# Sauna.net
KiCad netlist of a schematic drawn in EAGLE
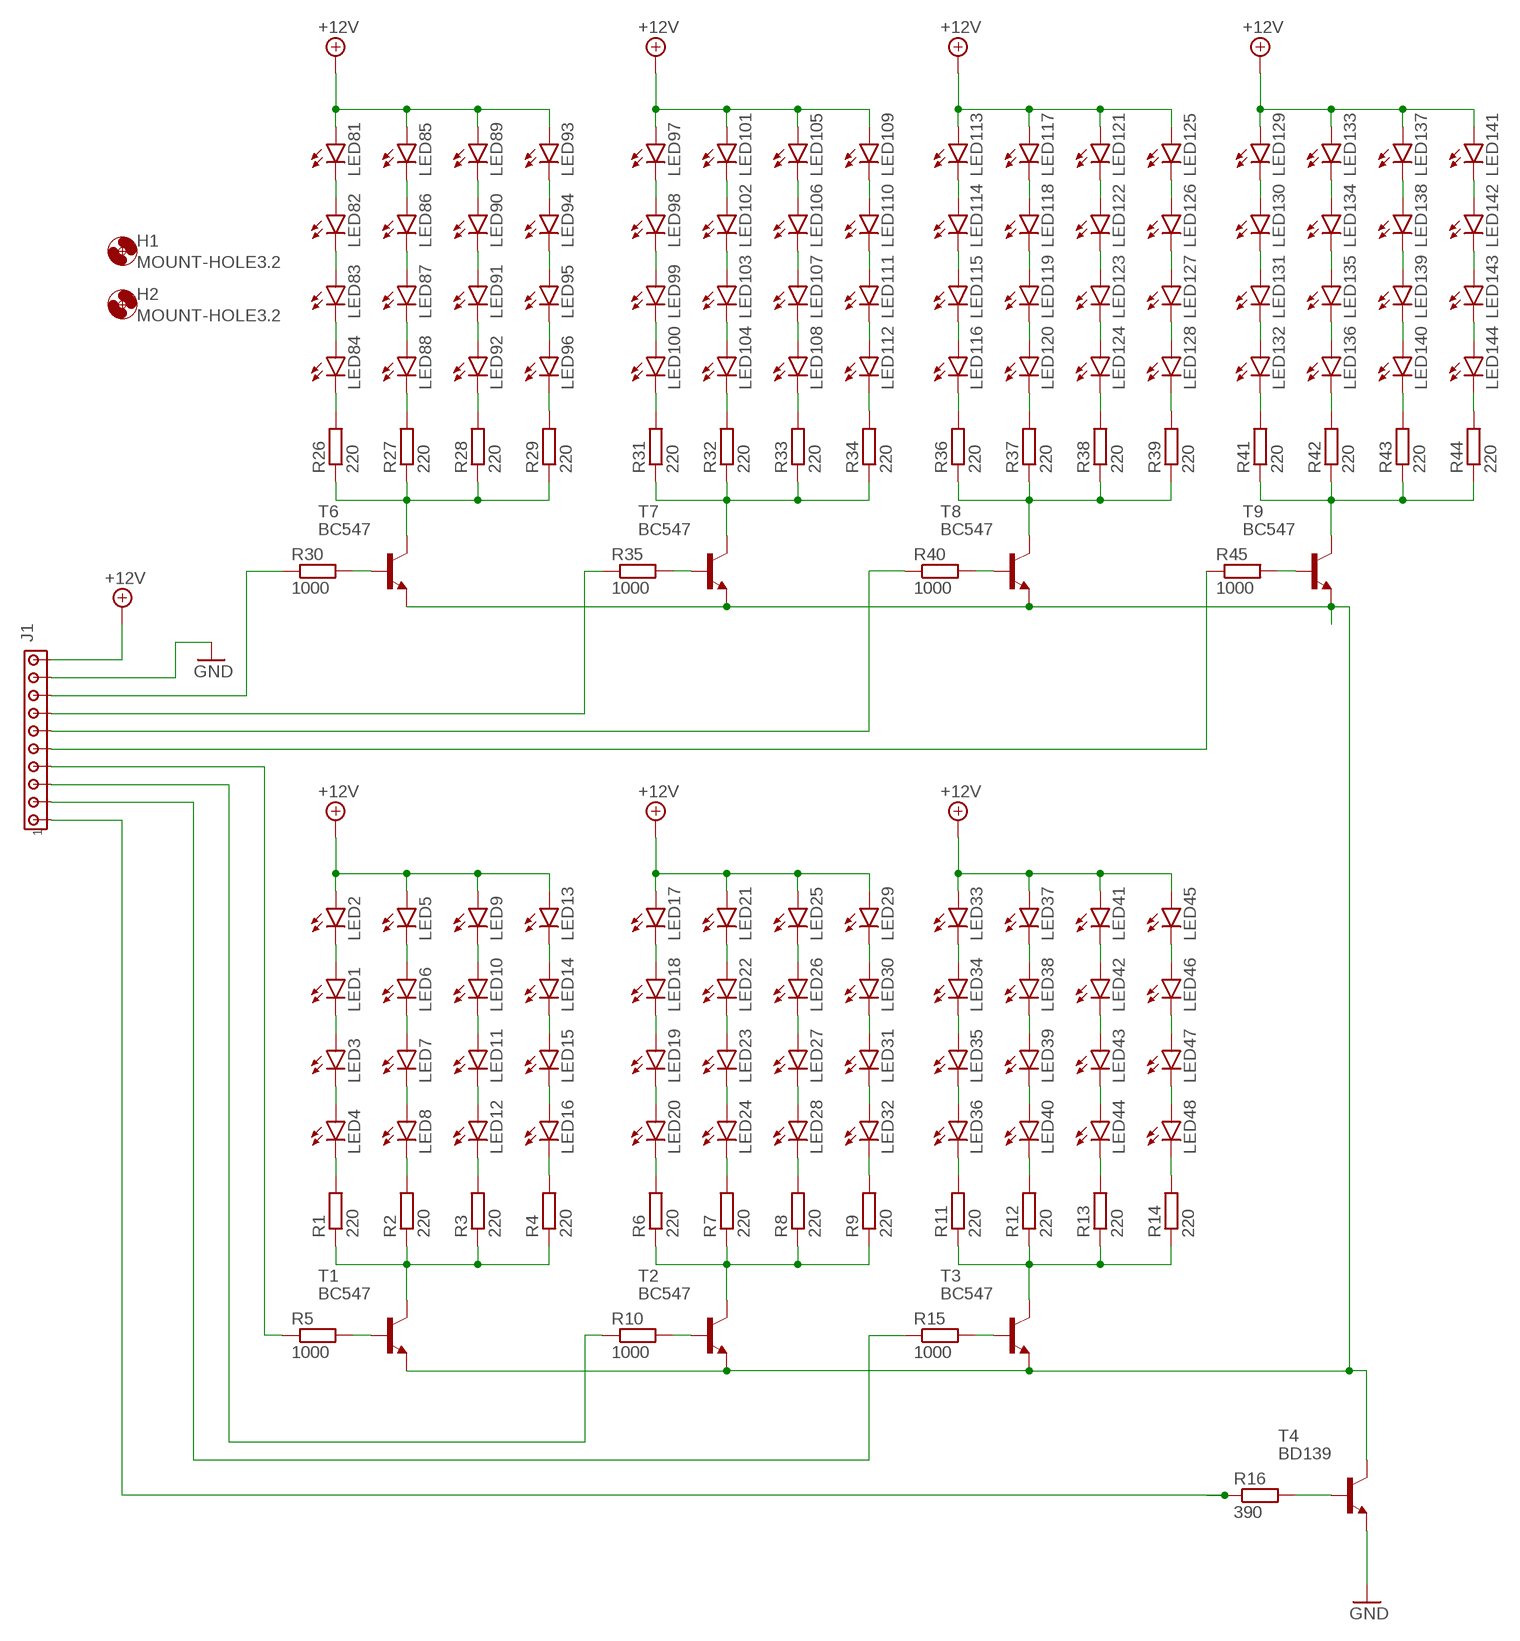
[diagram p0: schematic, sheet 1]

(export (version "E")
  (design (tool "Eeschema 10.0.6"))
  (components
    (comp (ref "H1")
      (value "MOUNT-HOLE3.2")
      (footprint "eagle-import:3,2")
      (libsource (lib "eagle-import") (part "MOUNT-HOLE3.2"))
    )
    (comp (ref "H2")
      (value "MOUNT-HOLE3.2")
      (footprint "eagle-import:3,2")
      (libsource (lib "eagle-import") (part "MOUNT-HOLE3.2"))
    )
    (comp (ref "J1")
      (value "MTA10-100")
      (footprint "eagle-import:10X10MTA")
      (libsource (lib "eagle-import") (part "MTA10-100"))
    )
    (comp (ref "LED1")
      (value "LED5MM")
      (footprint "eagle-import:LED5MM")
      (libsource (lib "eagle-import") (part "LED5MM"))
    )
    (comp (ref "LED2")
      (value "LED5MM")
      (footprint "eagle-import:LED5MM")
      (libsource (lib "eagle-import") (part "LED5MM"))
    )
    (comp (ref "LED3")
      (value "LED5MM")
      (footprint "eagle-import:LED5MM")
      (libsource (lib "eagle-import") (part "LED5MM"))
    )
    (comp (ref "LED4")
      (value "LED5MM")
      (footprint "eagle-import:LED5MM")
      (libsource (lib "eagle-import") (part "LED5MM"))
    )
    (comp (ref "LED5")
      (value "LED5MM")
      (footprint "eagle-import:LED5MM")
      (libsource (lib "eagle-import") (part "LED5MM"))
    )
    (comp (ref "LED6")
      (value "LED5MM")
      (footprint "eagle-import:LED5MM")
      (libsource (lib "eagle-import") (part "LED5MM"))
    )
    (comp (ref "LED7")
      (value "LED5MM")
      (footprint "eagle-import:LED5MM")
      (libsource (lib "eagle-import") (part "LED5MM"))
    )
    (comp (ref "LED8")
      (value "LED5MM")
      (footprint "eagle-import:LED5MM")
      (libsource (lib "eagle-import") (part "LED5MM"))
    )
    (comp (ref "LED9")
      (value "LED5MM")
      (footprint "eagle-import:LED5MM")
      (libsource (lib "eagle-import") (part "LED5MM"))
    )
    (comp (ref "LED10")
      (value "LED5MM")
      (footprint "eagle-import:LED5MM")
      (libsource (lib "eagle-import") (part "LED5MM"))
    )
    (comp (ref "LED11")
      (value "LED5MM")
      (footprint "eagle-import:LED5MM")
      (libsource (lib "eagle-import") (part "LED5MM"))
    )
    (comp (ref "LED12")
      (value "LED5MM")
      (footprint "eagle-import:LED5MM")
      (libsource (lib "eagle-import") (part "LED5MM"))
    )
    (comp (ref "LED13")
      (value "LED5MM")
      (footprint "eagle-import:LED5MM")
      (libsource (lib "eagle-import") (part "LED5MM"))
    )
    (comp (ref "LED14")
      (value "LED5MM")
      (footprint "eagle-import:LED5MM")
      (libsource (lib "eagle-import") (part "LED5MM"))
    )
    (comp (ref "LED15")
      (value "LED5MM")
      (footprint "eagle-import:LED5MM")
      (libsource (lib "eagle-import") (part "LED5MM"))
    )
    (comp (ref "LED16")
      (value "LED5MM")
      (footprint "eagle-import:LED5MM")
      (libsource (lib "eagle-import") (part "LED5MM"))
    )
    (comp (ref "LED17")
      (value "LED5MM")
      (footprint "eagle-import:LED5MM")
      (libsource (lib "eagle-import") (part "LED5MM"))
    )
    (comp (ref "LED18")
      (value "LED5MM")
      (footprint "eagle-import:LED5MM")
      (libsource (lib "eagle-import") (part "LED5MM"))
    )
    (comp (ref "LED19")
      (value "LED5MM")
      (footprint "eagle-import:LED5MM")
      (libsource (lib "eagle-import") (part "LED5MM"))
    )
    (comp (ref "LED20")
      (value "LED5MM")
      (footprint "eagle-import:LED5MM")
      (libsource (lib "eagle-import") (part "LED5MM"))
    )
    (comp (ref "LED21")
      (value "LED5MM")
      (footprint "eagle-import:LED5MM")
      (libsource (lib "eagle-import") (part "LED5MM"))
    )
    (comp (ref "LED22")
      (value "LED5MM")
      (footprint "eagle-import:LED5MM")
      (libsource (lib "eagle-import") (part "LED5MM"))
    )
    (comp (ref "LED23")
      (value "LED5MM")
      (footprint "eagle-import:LED5MM")
      (libsource (lib "eagle-import") (part "LED5MM"))
    )
    (comp (ref "LED24")
      (value "LED5MM")
      (footprint "eagle-import:LED5MM")
      (libsource (lib "eagle-import") (part "LED5MM"))
    )
    (comp (ref "LED25")
      (value "LED5MM")
      (footprint "eagle-import:LED5MM")
      (libsource (lib "eagle-import") (part "LED5MM"))
    )
    (comp (ref "LED26")
      (value "LED5MM")
      (footprint "eagle-import:LED5MM")
      (libsource (lib "eagle-import") (part "LED5MM"))
    )
    (comp (ref "LED27")
      (value "LED5MM")
      (footprint "eagle-import:LED5MM")
      (libsource (lib "eagle-import") (part "LED5MM"))
    )
    (comp (ref "LED28")
      (value "LED5MM")
      (footprint "eagle-import:LED5MM")
      (libsource (lib "eagle-import") (part "LED5MM"))
    )
    (comp (ref "LED29")
      (value "LED5MM")
      (footprint "eagle-import:LED5MM")
      (libsource (lib "eagle-import") (part "LED5MM"))
    )
    (comp (ref "LED30")
      (value "LED5MM")
      (footprint "eagle-import:LED5MM")
      (libsource (lib "eagle-import") (part "LED5MM"))
    )
    (comp (ref "LED31")
      (value "LED5MM")
      (footprint "eagle-import:LED5MM")
      (libsource (lib "eagle-import") (part "LED5MM"))
    )
    (comp (ref "LED32")
      (value "LED5MM")
      (footprint "eagle-import:LED5MM")
      (libsource (lib "eagle-import") (part "LED5MM"))
    )
    (comp (ref "LED33")
      (value "LED5MM")
      (footprint "eagle-import:LED5MM")
      (libsource (lib "eagle-import") (part "LED5MM"))
    )
    (comp (ref "LED34")
      (value "LED5MM")
      (footprint "eagle-import:LED5MM")
      (libsource (lib "eagle-import") (part "LED5MM"))
    )
    (comp (ref "LED35")
      (value "LED5MM")
      (footprint "eagle-import:LED5MM")
      (libsource (lib "eagle-import") (part "LED5MM"))
    )
    (comp (ref "LED36")
      (value "LED5MM")
      (footprint "eagle-import:LED5MM")
      (libsource (lib "eagle-import") (part "LED5MM"))
    )
    (comp (ref "LED37")
      (value "LED5MM")
      (footprint "eagle-import:LED5MM")
      (libsource (lib "eagle-import") (part "LED5MM"))
    )
    (comp (ref "LED38")
      (value "LED5MM")
      (footprint "eagle-import:LED5MM")
      (libsource (lib "eagle-import") (part "LED5MM"))
    )
    (comp (ref "LED39")
      (value "LED5MM")
      (footprint "eagle-import:LED5MM")
      (libsource (lib "eagle-import") (part "LED5MM"))
    )
    (comp (ref "LED40")
      (value "LED5MM")
      (footprint "eagle-import:LED5MM")
      (libsource (lib "eagle-import") (part "LED5MM"))
    )
    (comp (ref "LED41")
      (value "LED5MM")
      (footprint "eagle-import:LED5MM")
      (libsource (lib "eagle-import") (part "LED5MM"))
    )
    (comp (ref "LED42")
      (value "LED5MM")
      (footprint "eagle-import:LED5MM")
      (libsource (lib "eagle-import") (part "LED5MM"))
    )
    (comp (ref "LED43")
      (value "LED5MM")
      (footprint "eagle-import:LED5MM")
      (libsource (lib "eagle-import") (part "LED5MM"))
    )
    (comp (ref "LED44")
      (value "LED5MM")
      (footprint "eagle-import:LED5MM")
      (libsource (lib "eagle-import") (part "LED5MM"))
    )
    (comp (ref "LED45")
      (value "LED5MM")
      (footprint "eagle-import:LED5MM")
      (libsource (lib "eagle-import") (part "LED5MM"))
    )
    (comp (ref "LED46")
      (value "LED5MM")
      (footprint "eagle-import:LED5MM")
      (libsource (lib "eagle-import") (part "LED5MM"))
    )
    (comp (ref "LED47")
      (value "LED5MM")
      (footprint "eagle-import:LED5MM")
      (libsource (lib "eagle-import") (part "LED5MM"))
    )
    (comp (ref "LED48")
      (value "LED5MM")
      (footprint "eagle-import:LED5MM")
      (libsource (lib "eagle-import") (part "LED5MM"))
    )
    (comp (ref "LED81")
      (value "LED5MM")
      (footprint "eagle-import:LED5MM")
      (libsource (lib "eagle-import") (part "LED5MM"))
    )
    (comp (ref "LED82")
      (value "LED5MM")
      (footprint "eagle-import:LED5MM")
      (libsource (lib "eagle-import") (part "LED5MM"))
    )
    (comp (ref "LED83")
      (value "LED5MM")
      (footprint "eagle-import:LED5MM")
      (libsource (lib "eagle-import") (part "LED5MM"))
    )
    (comp (ref "LED84")
      (value "LED5MM")
      (footprint "eagle-import:LED5MM")
      (libsource (lib "eagle-import") (part "LED5MM"))
    )
    (comp (ref "LED85")
      (value "LED5MM")
      (footprint "eagle-import:LED5MM")
      (libsource (lib "eagle-import") (part "LED5MM"))
    )
    (comp (ref "LED86")
      (value "LED5MM")
      (footprint "eagle-import:LED5MM")
      (libsource (lib "eagle-import") (part "LED5MM"))
    )
    (comp (ref "LED87")
      (value "LED5MM")
      (footprint "eagle-import:LED5MM")
      (libsource (lib "eagle-import") (part "LED5MM"))
    )
    (comp (ref "LED88")
      (value "LED5MM")
      (footprint "eagle-import:LED5MM")
      (libsource (lib "eagle-import") (part "LED5MM"))
    )
    (comp (ref "LED89")
      (value "LED5MM")
      (footprint "eagle-import:LED5MM")
      (libsource (lib "eagle-import") (part "LED5MM"))
    )
    (comp (ref "LED90")
      (value "LED5MM")
      (footprint "eagle-import:LED5MM")
      (libsource (lib "eagle-import") (part "LED5MM"))
    )
    (comp (ref "LED91")
      (value "LED5MM")
      (footprint "eagle-import:LED5MM")
      (libsource (lib "eagle-import") (part "LED5MM"))
    )
    (comp (ref "LED92")
      (value "LED5MM")
      (footprint "eagle-import:LED5MM")
      (libsource (lib "eagle-import") (part "LED5MM"))
    )
    (comp (ref "LED93")
      (value "LED5MM")
      (footprint "eagle-import:LED5MM")
      (libsource (lib "eagle-import") (part "LED5MM"))
    )
    (comp (ref "LED94")
      (value "LED5MM")
      (footprint "eagle-import:LED5MM")
      (libsource (lib "eagle-import") (part "LED5MM"))
    )
    (comp (ref "LED95")
      (value "LED5MM")
      (footprint "eagle-import:LED5MM")
      (libsource (lib "eagle-import") (part "LED5MM"))
    )
    (comp (ref "LED96")
      (value "LED5MM")
      (footprint "eagle-import:LED5MM")
      (libsource (lib "eagle-import") (part "LED5MM"))
    )
    (comp (ref "LED97")
      (value "LED5MM")
      (footprint "eagle-import:LED5MM")
      (libsource (lib "eagle-import") (part "LED5MM"))
    )
    (comp (ref "LED98")
      (value "LED5MM")
      (footprint "eagle-import:LED5MM")
      (libsource (lib "eagle-import") (part "LED5MM"))
    )
    (comp (ref "LED99")
      (value "LED5MM")
      (footprint "eagle-import:LED5MM")
      (libsource (lib "eagle-import") (part "LED5MM"))
    )
    (comp (ref "LED100")
      (value "LED5MM")
      (footprint "eagle-import:LED5MM")
      (libsource (lib "eagle-import") (part "LED5MM"))
    )
    (comp (ref "LED101")
      (value "LED5MM")
      (footprint "eagle-import:LED5MM")
      (libsource (lib "eagle-import") (part "LED5MM"))
    )
    (comp (ref "LED102")
      (value "LED5MM")
      (footprint "eagle-import:LED5MM")
      (libsource (lib "eagle-import") (part "LED5MM"))
    )
    (comp (ref "LED103")
      (value "LED5MM")
      (footprint "eagle-import:LED5MM")
      (libsource (lib "eagle-import") (part "LED5MM"))
    )
    (comp (ref "LED104")
      (value "LED5MM")
      (footprint "eagle-import:LED5MM")
      (libsource (lib "eagle-import") (part "LED5MM"))
    )
    (comp (ref "LED105")
      (value "LED5MM")
      (footprint "eagle-import:LED5MM")
      (libsource (lib "eagle-import") (part "LED5MM"))
    )
    (comp (ref "LED106")
      (value "LED5MM")
      (footprint "eagle-import:LED5MM")
      (libsource (lib "eagle-import") (part "LED5MM"))
    )
    (comp (ref "LED107")
      (value "LED5MM")
      (footprint "eagle-import:LED5MM")
      (libsource (lib "eagle-import") (part "LED5MM"))
    )
    (comp (ref "LED108")
      (value "LED5MM")
      (footprint "eagle-import:LED5MM")
      (libsource (lib "eagle-import") (part "LED5MM"))
    )
    (comp (ref "LED109")
      (value "LED5MM")
      (footprint "eagle-import:LED5MM")
      (libsource (lib "eagle-import") (part "LED5MM"))
    )
    (comp (ref "LED110")
      (value "LED5MM")
      (footprint "eagle-import:LED5MM")
      (libsource (lib "eagle-import") (part "LED5MM"))
    )
    (comp (ref "LED111")
      (value "LED5MM")
      (footprint "eagle-import:LED5MM")
      (libsource (lib "eagle-import") (part "LED5MM"))
    )
    (comp (ref "LED112")
      (value "LED5MM")
      (footprint "eagle-import:LED5MM")
      (libsource (lib "eagle-import") (part "LED5MM"))
    )
    (comp (ref "LED113")
      (value "LED5MM")
      (footprint "eagle-import:LED5MM")
      (libsource (lib "eagle-import") (part "LED5MM"))
    )
    (comp (ref "LED114")
      (value "LED5MM")
      (footprint "eagle-import:LED5MM")
      (libsource (lib "eagle-import") (part "LED5MM"))
    )
    (comp (ref "LED115")
      (value "LED5MM")
      (footprint "eagle-import:LED5MM")
      (libsource (lib "eagle-import") (part "LED5MM"))
    )
    (comp (ref "LED116")
      (value "LED5MM")
      (footprint "eagle-import:LED5MM")
      (libsource (lib "eagle-import") (part "LED5MM"))
    )
    (comp (ref "LED117")
      (value "LED5MM")
      (footprint "eagle-import:LED5MM")
      (libsource (lib "eagle-import") (part "LED5MM"))
    )
    (comp (ref "LED118")
      (value "LED5MM")
      (footprint "eagle-import:LED5MM")
      (libsource (lib "eagle-import") (part "LED5MM"))
    )
    (comp (ref "LED119")
      (value "LED5MM")
      (footprint "eagle-import:LED5MM")
      (libsource (lib "eagle-import") (part "LED5MM"))
    )
    (comp (ref "LED120")
      (value "LED5MM")
      (footprint "eagle-import:LED5MM")
      (libsource (lib "eagle-import") (part "LED5MM"))
    )
    (comp (ref "LED121")
      (value "LED5MM")
      (footprint "eagle-import:LED5MM")
      (libsource (lib "eagle-import") (part "LED5MM"))
    )
    (comp (ref "LED122")
      (value "LED5MM")
      (footprint "eagle-import:LED5MM")
      (libsource (lib "eagle-import") (part "LED5MM"))
    )
    (comp (ref "LED123")
      (value "LED5MM")
      (footprint "eagle-import:LED5MM")
      (libsource (lib "eagle-import") (part "LED5MM"))
    )
    (comp (ref "LED124")
      (value "LED5MM")
      (footprint "eagle-import:LED5MM")
      (libsource (lib "eagle-import") (part "LED5MM"))
    )
    (comp (ref "LED125")
      (value "LED5MM")
      (footprint "eagle-import:LED5MM")
      (libsource (lib "eagle-import") (part "LED5MM"))
    )
    (comp (ref "LED126")
      (value "LED5MM")
      (footprint "eagle-import:LED5MM")
      (libsource (lib "eagle-import") (part "LED5MM"))
    )
    (comp (ref "LED127")
      (value "LED5MM")
      (footprint "eagle-import:LED5MM")
      (libsource (lib "eagle-import") (part "LED5MM"))
    )
    (comp (ref "LED128")
      (value "LED5MM")
      (footprint "eagle-import:LED5MM")
      (libsource (lib "eagle-import") (part "LED5MM"))
    )
    (comp (ref "LED129")
      (value "LED5MM")
      (footprint "eagle-import:LED5MM")
      (libsource (lib "eagle-import") (part "LED5MM"))
    )
    (comp (ref "LED130")
      (value "LED5MM")
      (footprint "eagle-import:LED5MM")
      (libsource (lib "eagle-import") (part "LED5MM"))
    )
    (comp (ref "LED131")
      (value "LED5MM")
      (footprint "eagle-import:LED5MM")
      (libsource (lib "eagle-import") (part "LED5MM"))
    )
    (comp (ref "LED132")
      (value "LED5MM")
      (footprint "eagle-import:LED5MM")
      (libsource (lib "eagle-import") (part "LED5MM"))
    )
    (comp (ref "LED133")
      (value "LED5MM")
      (footprint "eagle-import:LED5MM")
      (libsource (lib "eagle-import") (part "LED5MM"))
    )
    (comp (ref "LED134")
      (value "LED5MM")
      (footprint "eagle-import:LED5MM")
      (libsource (lib "eagle-import") (part "LED5MM"))
    )
    (comp (ref "LED135")
      (value "LED5MM")
      (footprint "eagle-import:LED5MM")
      (libsource (lib "eagle-import") (part "LED5MM"))
    )
    (comp (ref "LED136")
      (value "LED5MM")
      (footprint "eagle-import:LED5MM")
      (libsource (lib "eagle-import") (part "LED5MM"))
    )
    (comp (ref "LED137")
      (value "LED5MM")
      (footprint "eagle-import:LED5MM")
      (libsource (lib "eagle-import") (part "LED5MM"))
    )
    (comp (ref "LED138")
      (value "LED5MM")
      (footprint "eagle-import:LED5MM")
      (libsource (lib "eagle-import") (part "LED5MM"))
    )
    (comp (ref "LED139")
      (value "LED5MM")
      (footprint "eagle-import:LED5MM")
      (libsource (lib "eagle-import") (part "LED5MM"))
    )
    (comp (ref "LED140")
      (value "LED5MM")
      (footprint "eagle-import:LED5MM")
      (libsource (lib "eagle-import") (part "LED5MM"))
    )
    (comp (ref "LED141")
      (value "LED5MM")
      (footprint "eagle-import:LED5MM")
      (libsource (lib "eagle-import") (part "LED5MM"))
    )
    (comp (ref "LED142")
      (value "LED5MM")
      (footprint "eagle-import:LED5MM")
      (libsource (lib "eagle-import") (part "LED5MM"))
    )
    (comp (ref "LED143")
      (value "LED5MM")
      (footprint "eagle-import:LED5MM")
      (libsource (lib "eagle-import") (part "LED5MM"))
    )
    (comp (ref "LED144")
      (value "LED5MM")
      (footprint "eagle-import:LED5MM")
      (libsource (lib "eagle-import") (part "LED5MM"))
    )
    (comp (ref "R1")
      (value "220")
      (footprint "eagle-import:0207_10")
      (libsource (lib "eagle-import") (part "R-EU_0207/10"))
    )
    (comp (ref "R2")
      (value "220")
      (footprint "eagle-import:0207_10")
      (libsource (lib "eagle-import") (part "R-EU_0207/10"))
    )
    (comp (ref "R3")
      (value "220")
      (footprint "eagle-import:0207_10")
      (libsource (lib "eagle-import") (part "R-EU_0207/10"))
    )
    (comp (ref "R4")
      (value "220")
      (footprint "eagle-import:0207_10")
      (libsource (lib "eagle-import") (part "R-EU_0207/10"))
    )
    (comp (ref "R5")
      (value "1000")
      (footprint "eagle-import:0207_10")
      (libsource (lib "eagle-import") (part "R-EU_0207/10"))
    )
    (comp (ref "R6")
      (value "220")
      (footprint "eagle-import:0207_10")
      (libsource (lib "eagle-import") (part "R-EU_0207/10"))
    )
    (comp (ref "R7")
      (value "220")
      (footprint "eagle-import:0207_10")
      (libsource (lib "eagle-import") (part "R-EU_0207/10"))
    )
    (comp (ref "R8")
      (value "220")
      (footprint "eagle-import:0207_10")
      (libsource (lib "eagle-import") (part "R-EU_0207/10"))
    )
    (comp (ref "R9")
      (value "220")
      (footprint "eagle-import:0207_10")
      (libsource (lib "eagle-import") (part "R-EU_0207/10"))
    )
    (comp (ref "R10")
      (value "1000")
      (footprint "eagle-import:0207_10")
      (libsource (lib "eagle-import") (part "R-EU_0207/10"))
    )
    (comp (ref "R11")
      (value "220")
      (footprint "eagle-import:0207_10")
      (libsource (lib "eagle-import") (part "R-EU_0207/10"))
    )
    (comp (ref "R12")
      (value "220")
      (footprint "eagle-import:0207_10")
      (libsource (lib "eagle-import") (part "R-EU_0207/10"))
    )
    (comp (ref "R13")
      (value "220")
      (footprint "eagle-import:0207_10")
      (libsource (lib "eagle-import") (part "R-EU_0207/10"))
    )
    (comp (ref "R14")
      (value "220")
      (footprint "eagle-import:0207_10")
      (libsource (lib "eagle-import") (part "R-EU_0207/10"))
    )
    (comp (ref "R15")
      (value "1000")
      (footprint "eagle-import:0207_10")
      (libsource (lib "eagle-import") (part "R-EU_0207/10"))
    )
    (comp (ref "R16")
      (value "390")
      (footprint "eagle-import:0207_10")
      (libsource (lib "eagle-import") (part "R-EU_0207/10"))
    )
    (comp (ref "R26")
      (value "220")
      (footprint "eagle-import:0207_10")
      (libsource (lib "eagle-import") (part "R-EU_0207/10"))
    )
    (comp (ref "R27")
      (value "220")
      (footprint "eagle-import:0207_10")
      (libsource (lib "eagle-import") (part "R-EU_0207/10"))
    )
    (comp (ref "R28")
      (value "220")
      (footprint "eagle-import:0207_10")
      (libsource (lib "eagle-import") (part "R-EU_0207/10"))
    )
    (comp (ref "R29")
      (value "220")
      (footprint "eagle-import:0207_10")
      (libsource (lib "eagle-import") (part "R-EU_0207/10"))
    )
    (comp (ref "R30")
      (value "1000")
      (footprint "eagle-import:0207_10")
      (libsource (lib "eagle-import") (part "R-EU_0207/10"))
    )
    (comp (ref "R31")
      (value "220")
      (footprint "eagle-import:0207_10")
      (libsource (lib "eagle-import") (part "R-EU_0207/10"))
    )
    (comp (ref "R32")
      (value "220")
      (footprint "eagle-import:0207_10")
      (libsource (lib "eagle-import") (part "R-EU_0207/10"))
    )
    (comp (ref "R33")
      (value "220")
      (footprint "eagle-import:0207_10")
      (libsource (lib "eagle-import") (part "R-EU_0207/10"))
    )
    (comp (ref "R34")
      (value "220")
      (footprint "eagle-import:0207_10")
      (libsource (lib "eagle-import") (part "R-EU_0207/10"))
    )
    (comp (ref "R35")
      (value "1000")
      (footprint "eagle-import:0207_10")
      (libsource (lib "eagle-import") (part "R-EU_0207/10"))
    )
    (comp (ref "R36")
      (value "220")
      (footprint "eagle-import:0207_10")
      (libsource (lib "eagle-import") (part "R-EU_0207/10"))
    )
    (comp (ref "R37")
      (value "220")
      (footprint "eagle-import:0207_10")
      (libsource (lib "eagle-import") (part "R-EU_0207/10"))
    )
    (comp (ref "R38")
      (value "220")
      (footprint "eagle-import:0207_10")
      (libsource (lib "eagle-import") (part "R-EU_0207/10"))
    )
    (comp (ref "R39")
      (value "220")
      (footprint "eagle-import:0207_10")
      (libsource (lib "eagle-import") (part "R-EU_0207/10"))
    )
    (comp (ref "R40")
      (value "1000")
      (footprint "eagle-import:0207_10")
      (libsource (lib "eagle-import") (part "R-EU_0207/10"))
    )
    (comp (ref "R41")
      (value "220")
      (footprint "eagle-import:0207_10")
      (libsource (lib "eagle-import") (part "R-EU_0207/10"))
    )
    (comp (ref "R42")
      (value "220")
      (footprint "eagle-import:0207_10")
      (libsource (lib "eagle-import") (part "R-EU_0207/10"))
    )
    (comp (ref "R43")
      (value "220")
      (footprint "eagle-import:0207_10")
      (libsource (lib "eagle-import") (part "R-EU_0207/10"))
    )
    (comp (ref "R44")
      (value "220")
      (footprint "eagle-import:0207_10")
      (libsource (lib "eagle-import") (part "R-EU_0207/10"))
    )
    (comp (ref "R45")
      (value "1000")
      (footprint "eagle-import:0207_10")
      (libsource (lib "eagle-import") (part "R-EU_0207/10"))
    )
    (comp (ref "T1")
      (value "BC547")
      (footprint "eagle-import:TO92")
      (libsource (lib "eagle-import") (part "BC547"))
    )
    (comp (ref "T2")
      (value "BC547")
      (footprint "eagle-import:TO92")
      (libsource (lib "eagle-import") (part "BC547"))
    )
    (comp (ref "T3")
      (value "BC547")
      (footprint "eagle-import:TO92")
      (libsource (lib "eagle-import") (part "BC547"))
    )
    (comp (ref "T4")
      (value "BD139")
      (footprint "eagle-import:TO126")
      (libsource (lib "eagle-import") (part "BD139"))
    )
    (comp (ref "T6")
      (value "BC547")
      (footprint "eagle-import:TO92")
      (libsource (lib "eagle-import") (part "BC547"))
    )
    (comp (ref "T7")
      (value "BC547")
      (footprint "eagle-import:TO92")
      (libsource (lib "eagle-import") (part "BC547"))
    )
    (comp (ref "T8")
      (value "BC547")
      (footprint "eagle-import:TO92")
      (libsource (lib "eagle-import") (part "BC547"))
    )
    (comp (ref "T9")
      (value "BC547")
      (footprint "eagle-import:TO92")
      (libsource (lib "eagle-import") (part "BC547"))
    )
  )
  (nets
    (net (code "1") (name "+12V") (class "Default")
      (node (ref "J1") (pin "10") (pinfunction "10_10") (pintype "passive"))
      (node (ref "LED101") (pin "A") (pinfunction "A_A") (pintype "passive"))
      (node (ref "LED105") (pin "A") (pinfunction "A_A") (pintype "passive"))
      (node (ref "LED109") (pin "A") (pinfunction "A_A") (pintype "passive"))
      (node (ref "LED113") (pin "A") (pinfunction "A_A") (pintype "passive"))
      (node (ref "LED117") (pin "A") (pinfunction "A_A") (pintype "passive"))
      (node (ref "LED121") (pin "A") (pinfunction "A_A") (pintype "passive"))
      (node (ref "LED125") (pin "A") (pinfunction "A_A") (pintype "passive"))
      (node (ref "LED129") (pin "A") (pinfunction "A_A") (pintype "passive"))
      (node (ref "LED13") (pin "A") (pinfunction "A_A") (pintype "passive"))
      (node (ref "LED133") (pin "A") (pinfunction "A_A") (pintype "passive"))
      (node (ref "LED137") (pin "A") (pinfunction "A_A") (pintype "passive"))
      (node (ref "LED141") (pin "A") (pinfunction "A_A") (pintype "passive"))
      (node (ref "LED17") (pin "A") (pinfunction "A_A") (pintype "passive"))
      (node (ref "LED2") (pin "A") (pinfunction "A_A") (pintype "passive"))
      (node (ref "LED21") (pin "A") (pinfunction "A_A") (pintype "passive"))
      (node (ref "LED25") (pin "A") (pinfunction "A_A") (pintype "passive"))
      (node (ref "LED29") (pin "A") (pinfunction "A_A") (pintype "passive"))
      (node (ref "LED33") (pin "A") (pinfunction "A_A") (pintype "passive"))
      (node (ref "LED37") (pin "A") (pinfunction "A_A") (pintype "passive"))
      (node (ref "LED41") (pin "A") (pinfunction "A_A") (pintype "passive"))
      (node (ref "LED45") (pin "A") (pinfunction "A_A") (pintype "passive"))
      (node (ref "LED5") (pin "A") (pinfunction "A_A") (pintype "passive"))
      (node (ref "LED81") (pin "A") (pinfunction "A_A") (pintype "passive"))
      (node (ref "LED85") (pin "A") (pinfunction "A_A") (pintype "passive"))
      (node (ref "LED89") (pin "A") (pinfunction "A_A") (pintype "passive"))
      (node (ref "LED9") (pin "A") (pinfunction "A_A") (pintype "passive"))
      (node (ref "LED93") (pin "A") (pinfunction "A_A") (pintype "passive"))
      (node (ref "LED97") (pin "A") (pinfunction "A_A") (pintype "passive"))
    )
    (net (code "2") (name "GND") (class "Default")
      (node (ref "J1") (pin "9") (pinfunction "9_9") (pintype "passive"))
      (node (ref "T4") (pin "1") (pinfunction "E_1") (pintype "passive"))
    )
    (net (code "3") (name "Net-(J1-Pad1)") (class "Default")
      (node (ref "J1") (pin "1") (pinfunction "1_1") (pintype "passive"))
      (node (ref "R16") (pin "1") (pinfunction "1_1") (pintype "passive"))
    )
    (net (code "4") (name "Net-(J1-Pad2)") (class "Default")
      (node (ref "J1") (pin "2") (pinfunction "2_2") (pintype "passive"))
      (node (ref "R15") (pin "1") (pinfunction "1_1") (pintype "passive"))
    )
    (net (code "5") (name "Net-(J1-Pad3)") (class "Default")
      (node (ref "J1") (pin "3") (pinfunction "3_3") (pintype "passive"))
      (node (ref "R10") (pin "1") (pinfunction "1_1") (pintype "passive"))
    )
    (net (code "6") (name "Net-(J1-Pad4)") (class "Default")
      (node (ref "J1") (pin "4") (pinfunction "4_4") (pintype "passive"))
      (node (ref "R5") (pin "1") (pinfunction "1_1") (pintype "passive"))
    )
    (net (code "7") (name "Net-(J1-Pad5)") (class "Default")
      (node (ref "J1") (pin "5") (pinfunction "5_5") (pintype "passive"))
      (node (ref "R45") (pin "1") (pinfunction "1_1") (pintype "passive"))
    )
    (net (code "8") (name "Net-(J1-Pad6)") (class "Default")
      (node (ref "J1") (pin "6") (pinfunction "6_6") (pintype "passive"))
      (node (ref "R40") (pin "1") (pinfunction "1_1") (pintype "passive"))
    )
    (net (code "9") (name "Net-(J1-Pad7)") (class "Default")
      (node (ref "J1") (pin "7") (pinfunction "7_7") (pintype "passive"))
      (node (ref "R35") (pin "1") (pinfunction "1_1") (pintype "passive"))
    )
    (net (code "10") (name "Net-(J1-Pad8)") (class "Default")
      (node (ref "J1") (pin "8") (pinfunction "8_8") (pintype "passive"))
      (node (ref "R30") (pin "1") (pinfunction "1_1") (pintype "passive"))
    )
    (net (code "11") (name "Net-(LED1-C)") (class "Default")
      (node (ref "LED1") (pin "K") (pinfunction "C_K") (pintype "passive"))
      (node (ref "LED3") (pin "A") (pinfunction "A_A") (pintype "passive"))
    )
    (net (code "12") (name "Net-(LED2-C)") (class "Default")
      (node (ref "LED1") (pin "A") (pinfunction "A_A") (pintype "passive"))
      (node (ref "LED2") (pin "K") (pinfunction "C_K") (pintype "passive"))
    )
    (net (code "13") (name "Net-(LED3-C)") (class "Default")
      (node (ref "LED3") (pin "K") (pinfunction "C_K") (pintype "passive"))
      (node (ref "LED4") (pin "A") (pinfunction "A_A") (pintype "passive"))
    )
    (net (code "14") (name "Net-(LED4-C)") (class "Default")
      (node (ref "LED4") (pin "K") (pinfunction "C_K") (pintype "passive"))
      (node (ref "R1") (pin "2") (pinfunction "2_2") (pintype "passive"))
    )
    (net (code "15") (name "Net-(LED5-C)") (class "Default")
      (node (ref "LED5") (pin "K") (pinfunction "C_K") (pintype "passive"))
      (node (ref "LED6") (pin "A") (pinfunction "A_A") (pintype "passive"))
    )
    (net (code "16") (name "Net-(LED6-C)") (class "Default")
      (node (ref "LED6") (pin "K") (pinfunction "C_K") (pintype "passive"))
      (node (ref "LED7") (pin "A") (pinfunction "A_A") (pintype "passive"))
    )
    (net (code "17") (name "Net-(LED7-C)") (class "Default")
      (node (ref "LED7") (pin "K") (pinfunction "C_K") (pintype "passive"))
      (node (ref "LED8") (pin "A") (pinfunction "A_A") (pintype "passive"))
    )
    (net (code "18") (name "Net-(LED8-C)") (class "Default")
      (node (ref "LED8") (pin "K") (pinfunction "C_K") (pintype "passive"))
      (node (ref "R2") (pin "2") (pinfunction "2_2") (pintype "passive"))
    )
    (net (code "19") (name "Net-(LED9-C)") (class "Default")
      (node (ref "LED10") (pin "A") (pinfunction "A_A") (pintype "passive"))
      (node (ref "LED9") (pin "K") (pinfunction "C_K") (pintype "passive"))
    )
    (net (code "20") (name "Net-(LED10-C)") (class "Default")
      (node (ref "LED10") (pin "K") (pinfunction "C_K") (pintype "passive"))
      (node (ref "LED11") (pin "A") (pinfunction "A_A") (pintype "passive"))
    )
    (net (code "21") (name "Net-(LED11-C)") (class "Default")
      (node (ref "LED11") (pin "K") (pinfunction "C_K") (pintype "passive"))
      (node (ref "LED12") (pin "A") (pinfunction "A_A") (pintype "passive"))
    )
    (net (code "22") (name "Net-(LED12-C)") (class "Default")
      (node (ref "LED12") (pin "K") (pinfunction "C_K") (pintype "passive"))
      (node (ref "R3") (pin "2") (pinfunction "2_2") (pintype "passive"))
    )
    (net (code "23") (name "Net-(LED13-C)") (class "Default")
      (node (ref "LED13") (pin "K") (pinfunction "C_K") (pintype "passive"))
      (node (ref "LED14") (pin "A") (pinfunction "A_A") (pintype "passive"))
    )
    (net (code "24") (name "Net-(LED14-C)") (class "Default")
      (node (ref "LED14") (pin "K") (pinfunction "C_K") (pintype "passive"))
      (node (ref "LED15") (pin "A") (pinfunction "A_A") (pintype "passive"))
    )
    (net (code "25") (name "Net-(LED15-C)") (class "Default")
      (node (ref "LED15") (pin "K") (pinfunction "C_K") (pintype "passive"))
      (node (ref "LED16") (pin "A") (pinfunction "A_A") (pintype "passive"))
    )
    (net (code "26") (name "Net-(LED16-C)") (class "Default")
      (node (ref "LED16") (pin "K") (pinfunction "C_K") (pintype "passive"))
      (node (ref "R4") (pin "2") (pinfunction "2_2") (pintype "passive"))
    )
    (net (code "27") (name "Net-(LED17-C)") (class "Default")
      (node (ref "LED17") (pin "K") (pinfunction "C_K") (pintype "passive"))
      (node (ref "LED18") (pin "A") (pinfunction "A_A") (pintype "passive"))
    )
    (net (code "28") (name "Net-(LED18-C)") (class "Default")
      (node (ref "LED18") (pin "K") (pinfunction "C_K") (pintype "passive"))
      (node (ref "LED19") (pin "A") (pinfunction "A_A") (pintype "passive"))
    )
    (net (code "29") (name "Net-(LED19-C)") (class "Default")
      (node (ref "LED19") (pin "K") (pinfunction "C_K") (pintype "passive"))
      (node (ref "LED20") (pin "A") (pinfunction "A_A") (pintype "passive"))
    )
    (net (code "30") (name "Net-(LED20-C)") (class "Default")
      (node (ref "LED20") (pin "K") (pinfunction "C_K") (pintype "passive"))
      (node (ref "R6") (pin "2") (pinfunction "2_2") (pintype "passive"))
    )
    (net (code "31") (name "Net-(LED21-C)") (class "Default")
      (node (ref "LED21") (pin "K") (pinfunction "C_K") (pintype "passive"))
      (node (ref "LED22") (pin "A") (pinfunction "A_A") (pintype "passive"))
    )
    (net (code "32") (name "Net-(LED22-C)") (class "Default")
      (node (ref "LED22") (pin "K") (pinfunction "C_K") (pintype "passive"))
      (node (ref "LED23") (pin "A") (pinfunction "A_A") (pintype "passive"))
    )
    (net (code "33") (name "Net-(LED23-C)") (class "Default")
      (node (ref "LED23") (pin "K") (pinfunction "C_K") (pintype "passive"))
      (node (ref "LED24") (pin "A") (pinfunction "A_A") (pintype "passive"))
    )
    (net (code "34") (name "Net-(LED24-C)") (class "Default")
      (node (ref "LED24") (pin "K") (pinfunction "C_K") (pintype "passive"))
      (node (ref "R7") (pin "2") (pinfunction "2_2") (pintype "passive"))
    )
    (net (code "35") (name "Net-(LED25-C)") (class "Default")
      (node (ref "LED25") (pin "K") (pinfunction "C_K") (pintype "passive"))
      (node (ref "LED26") (pin "A") (pinfunction "A_A") (pintype "passive"))
    )
    (net (code "36") (name "Net-(LED26-C)") (class "Default")
      (node (ref "LED26") (pin "K") (pinfunction "C_K") (pintype "passive"))
      (node (ref "LED27") (pin "A") (pinfunction "A_A") (pintype "passive"))
    )
    (net (code "37") (name "Net-(LED27-C)") (class "Default")
      (node (ref "LED27") (pin "K") (pinfunction "C_K") (pintype "passive"))
      (node (ref "LED28") (pin "A") (pinfunction "A_A") (pintype "passive"))
    )
    (net (code "38") (name "Net-(LED28-C)") (class "Default")
      (node (ref "LED28") (pin "K") (pinfunction "C_K") (pintype "passive"))
      (node (ref "R8") (pin "2") (pinfunction "2_2") (pintype "passive"))
    )
    (net (code "39") (name "Net-(LED29-C)") (class "Default")
      (node (ref "LED29") (pin "K") (pinfunction "C_K") (pintype "passive"))
      (node (ref "LED30") (pin "A") (pinfunction "A_A") (pintype "passive"))
    )
    (net (code "40") (name "Net-(LED30-C)") (class "Default")
      (node (ref "LED30") (pin "K") (pinfunction "C_K") (pintype "passive"))
      (node (ref "LED31") (pin "A") (pinfunction "A_A") (pintype "passive"))
    )
    (net (code "41") (name "Net-(LED31-C)") (class "Default")
      (node (ref "LED31") (pin "K") (pinfunction "C_K") (pintype "passive"))
      (node (ref "LED32") (pin "A") (pinfunction "A_A") (pintype "passive"))
    )
    (net (code "42") (name "Net-(LED32-C)") (class "Default")
      (node (ref "LED32") (pin "K") (pinfunction "C_K") (pintype "passive"))
      (node (ref "R9") (pin "2") (pinfunction "2_2") (pintype "passive"))
    )
    (net (code "43") (name "Net-(LED33-C)") (class "Default")
      (node (ref "LED33") (pin "K") (pinfunction "C_K") (pintype "passive"))
      (node (ref "LED34") (pin "A") (pinfunction "A_A") (pintype "passive"))
    )
    (net (code "44") (name "Net-(LED34-C)") (class "Default")
      (node (ref "LED34") (pin "K") (pinfunction "C_K") (pintype "passive"))
      (node (ref "LED35") (pin "A") (pinfunction "A_A") (pintype "passive"))
    )
    (net (code "45") (name "Net-(LED35-C)") (class "Default")
      (node (ref "LED35") (pin "K") (pinfunction "C_K") (pintype "passive"))
      (node (ref "LED36") (pin "A") (pinfunction "A_A") (pintype "passive"))
    )
    (net (code "46") (name "Net-(LED36-C)") (class "Default")
      (node (ref "LED36") (pin "K") (pinfunction "C_K") (pintype "passive"))
      (node (ref "R11") (pin "2") (pinfunction "2_2") (pintype "passive"))
    )
    (net (code "47") (name "Net-(LED37-C)") (class "Default")
      (node (ref "LED37") (pin "K") (pinfunction "C_K") (pintype "passive"))
      (node (ref "LED38") (pin "A") (pinfunction "A_A") (pintype "passive"))
    )
    (net (code "48") (name "Net-(LED38-C)") (class "Default")
      (node (ref "LED38") (pin "K") (pinfunction "C_K") (pintype "passive"))
      (node (ref "LED39") (pin "A") (pinfunction "A_A") (pintype "passive"))
    )
    (net (code "49") (name "Net-(LED39-C)") (class "Default")
      (node (ref "LED39") (pin "K") (pinfunction "C_K") (pintype "passive"))
      (node (ref "LED40") (pin "A") (pinfunction "A_A") (pintype "passive"))
    )
    (net (code "50") (name "Net-(LED40-C)") (class "Default")
      (node (ref "LED40") (pin "K") (pinfunction "C_K") (pintype "passive"))
      (node (ref "R12") (pin "2") (pinfunction "2_2") (pintype "passive"))
    )
    (net (code "51") (name "Net-(LED41-C)") (class "Default")
      (node (ref "LED41") (pin "K") (pinfunction "C_K") (pintype "passive"))
      (node (ref "LED42") (pin "A") (pinfunction "A_A") (pintype "passive"))
    )
    (net (code "52") (name "Net-(LED42-C)") (class "Default")
      (node (ref "LED42") (pin "K") (pinfunction "C_K") (pintype "passive"))
      (node (ref "LED43") (pin "A") (pinfunction "A_A") (pintype "passive"))
    )
    (net (code "53") (name "Net-(LED43-C)") (class "Default")
      (node (ref "LED43") (pin "K") (pinfunction "C_K") (pintype "passive"))
      (node (ref "LED44") (pin "A") (pinfunction "A_A") (pintype "passive"))
    )
    (net (code "54") (name "Net-(LED44-C)") (class "Default")
      (node (ref "LED44") (pin "K") (pinfunction "C_K") (pintype "passive"))
      (node (ref "R13") (pin "2") (pinfunction "2_2") (pintype "passive"))
    )
    (net (code "55") (name "Net-(LED45-C)") (class "Default")
      (node (ref "LED45") (pin "K") (pinfunction "C_K") (pintype "passive"))
      (node (ref "LED46") (pin "A") (pinfunction "A_A") (pintype "passive"))
    )
    (net (code "56") (name "Net-(LED46-C)") (class "Default")
      (node (ref "LED46") (pin "K") (pinfunction "C_K") (pintype "passive"))
      (node (ref "LED47") (pin "A") (pinfunction "A_A") (pintype "passive"))
    )
    (net (code "57") (name "Net-(LED47-C)") (class "Default")
      (node (ref "LED47") (pin "K") (pinfunction "C_K") (pintype "passive"))
      (node (ref "LED48") (pin "A") (pinfunction "A_A") (pintype "passive"))
    )
    (net (code "58") (name "Net-(LED48-C)") (class "Default")
      (node (ref "LED48") (pin "K") (pinfunction "C_K") (pintype "passive"))
      (node (ref "R14") (pin "2") (pinfunction "2_2") (pintype "passive"))
    )
    (net (code "59") (name "Net-(LED81-C)") (class "Default")
      (node (ref "LED81") (pin "K") (pinfunction "C_K") (pintype "passive"))
      (node (ref "LED82") (pin "A") (pinfunction "A_A") (pintype "passive"))
    )
    (net (code "60") (name "Net-(LED82-C)") (class "Default")
      (node (ref "LED82") (pin "K") (pinfunction "C_K") (pintype "passive"))
      (node (ref "LED83") (pin "A") (pinfunction "A_A") (pintype "passive"))
    )
    (net (code "61") (name "Net-(LED83-C)") (class "Default")
      (node (ref "LED83") (pin "K") (pinfunction "C_K") (pintype "passive"))
      (node (ref "LED84") (pin "A") (pinfunction "A_A") (pintype "passive"))
    )
    (net (code "62") (name "Net-(LED84-C)") (class "Default")
      (node (ref "LED84") (pin "K") (pinfunction "C_K") (pintype "passive"))
      (node (ref "R26") (pin "2") (pinfunction "2_2") (pintype "passive"))
    )
    (net (code "63") (name "Net-(LED85-C)") (class "Default")
      (node (ref "LED85") (pin "K") (pinfunction "C_K") (pintype "passive"))
      (node (ref "LED86") (pin "A") (pinfunction "A_A") (pintype "passive"))
    )
    (net (code "64") (name "Net-(LED86-C)") (class "Default")
      (node (ref "LED86") (pin "K") (pinfunction "C_K") (pintype "passive"))
      (node (ref "LED87") (pin "A") (pinfunction "A_A") (pintype "passive"))
    )
    (net (code "65") (name "Net-(LED87-C)") (class "Default")
      (node (ref "LED87") (pin "K") (pinfunction "C_K") (pintype "passive"))
      (node (ref "LED88") (pin "A") (pinfunction "A_A") (pintype "passive"))
    )
    (net (code "66") (name "Net-(LED88-C)") (class "Default")
      (node (ref "LED88") (pin "K") (pinfunction "C_K") (pintype "passive"))
      (node (ref "R27") (pin "2") (pinfunction "2_2") (pintype "passive"))
    )
    (net (code "67") (name "Net-(LED89-C)") (class "Default")
      (node (ref "LED89") (pin "K") (pinfunction "C_K") (pintype "passive"))
      (node (ref "LED90") (pin "A") (pinfunction "A_A") (pintype "passive"))
    )
    (net (code "68") (name "Net-(LED90-C)") (class "Default")
      (node (ref "LED90") (pin "K") (pinfunction "C_K") (pintype "passive"))
      (node (ref "LED91") (pin "A") (pinfunction "A_A") (pintype "passive"))
    )
    (net (code "69") (name "Net-(LED91-C)") (class "Default")
      (node (ref "LED91") (pin "K") (pinfunction "C_K") (pintype "passive"))
      (node (ref "LED92") (pin "A") (pinfunction "A_A") (pintype "passive"))
    )
    (net (code "70") (name "Net-(LED92-C)") (class "Default")
      (node (ref "LED92") (pin "K") (pinfunction "C_K") (pintype "passive"))
      (node (ref "R28") (pin "2") (pinfunction "2_2") (pintype "passive"))
    )
    (net (code "71") (name "Net-(LED93-C)") (class "Default")
      (node (ref "LED93") (pin "K") (pinfunction "C_K") (pintype "passive"))
      (node (ref "LED94") (pin "A") (pinfunction "A_A") (pintype "passive"))
    )
    (net (code "72") (name "Net-(LED94-C)") (class "Default")
      (node (ref "LED94") (pin "K") (pinfunction "C_K") (pintype "passive"))
      (node (ref "LED95") (pin "A") (pinfunction "A_A") (pintype "passive"))
    )
    (net (code "73") (name "Net-(LED95-C)") (class "Default")
      (node (ref "LED95") (pin "K") (pinfunction "C_K") (pintype "passive"))
      (node (ref "LED96") (pin "A") (pinfunction "A_A") (pintype "passive"))
    )
    (net (code "74") (name "Net-(LED96-C)") (class "Default")
      (node (ref "LED96") (pin "K") (pinfunction "C_K") (pintype "passive"))
      (node (ref "R29") (pin "2") (pinfunction "2_2") (pintype "passive"))
    )
    (net (code "75") (name "Net-(LED97-C)") (class "Default")
      (node (ref "LED97") (pin "K") (pinfunction "C_K") (pintype "passive"))
      (node (ref "LED98") (pin "A") (pinfunction "A_A") (pintype "passive"))
    )
    (net (code "76") (name "Net-(LED98-C)") (class "Default")
      (node (ref "LED98") (pin "K") (pinfunction "C_K") (pintype "passive"))
      (node (ref "LED99") (pin "A") (pinfunction "A_A") (pintype "passive"))
    )
    (net (code "77") (name "Net-(LED99-C)") (class "Default")
      (node (ref "LED100") (pin "A") (pinfunction "A_A") (pintype "passive"))
      (node (ref "LED99") (pin "K") (pinfunction "C_K") (pintype "passive"))
    )
    (net (code "78") (name "Net-(LED100-C)") (class "Default")
      (node (ref "LED100") (pin "K") (pinfunction "C_K") (pintype "passive"))
      (node (ref "R31") (pin "2") (pinfunction "2_2") (pintype "passive"))
    )
    (net (code "79") (name "Net-(LED101-C)") (class "Default")
      (node (ref "LED101") (pin "K") (pinfunction "C_K") (pintype "passive"))
      (node (ref "LED102") (pin "A") (pinfunction "A_A") (pintype "passive"))
    )
    (net (code "80") (name "Net-(LED102-C)") (class "Default")
      (node (ref "LED102") (pin "K") (pinfunction "C_K") (pintype "passive"))
      (node (ref "LED103") (pin "A") (pinfunction "A_A") (pintype "passive"))
    )
    (net (code "81") (name "Net-(LED103-C)") (class "Default")
      (node (ref "LED103") (pin "K") (pinfunction "C_K") (pintype "passive"))
      (node (ref "LED104") (pin "A") (pinfunction "A_A") (pintype "passive"))
    )
    (net (code "82") (name "Net-(LED104-C)") (class "Default")
      (node (ref "LED104") (pin "K") (pinfunction "C_K") (pintype "passive"))
      (node (ref "R32") (pin "2") (pinfunction "2_2") (pintype "passive"))
    )
    (net (code "83") (name "Net-(LED105-C)") (class "Default")
      (node (ref "LED105") (pin "K") (pinfunction "C_K") (pintype "passive"))
      (node (ref "LED106") (pin "A") (pinfunction "A_A") (pintype "passive"))
    )
    (net (code "84") (name "Net-(LED106-C)") (class "Default")
      (node (ref "LED106") (pin "K") (pinfunction "C_K") (pintype "passive"))
      (node (ref "LED107") (pin "A") (pinfunction "A_A") (pintype "passive"))
    )
    (net (code "85") (name "Net-(LED107-C)") (class "Default")
      (node (ref "LED107") (pin "K") (pinfunction "C_K") (pintype "passive"))
      (node (ref "LED108") (pin "A") (pinfunction "A_A") (pintype "passive"))
    )
    (net (code "86") (name "Net-(LED108-C)") (class "Default")
      (node (ref "LED108") (pin "K") (pinfunction "C_K") (pintype "passive"))
      (node (ref "R33") (pin "2") (pinfunction "2_2") (pintype "passive"))
    )
    (net (code "87") (name "Net-(LED109-C)") (class "Default")
      (node (ref "LED109") (pin "K") (pinfunction "C_K") (pintype "passive"))
      (node (ref "LED110") (pin "A") (pinfunction "A_A") (pintype "passive"))
    )
    (net (code "88") (name "Net-(LED110-C)") (class "Default")
      (node (ref "LED110") (pin "K") (pinfunction "C_K") (pintype "passive"))
      (node (ref "LED111") (pin "A") (pinfunction "A_A") (pintype "passive"))
    )
    (net (code "89") (name "Net-(LED111-C)") (class "Default")
      (node (ref "LED111") (pin "K") (pinfunction "C_K") (pintype "passive"))
      (node (ref "LED112") (pin "A") (pinfunction "A_A") (pintype "passive"))
    )
    (net (code "90") (name "Net-(LED112-C)") (class "Default")
      (node (ref "LED112") (pin "K") (pinfunction "C_K") (pintype "passive"))
      (node (ref "R34") (pin "2") (pinfunction "2_2") (pintype "passive"))
    )
    (net (code "91") (name "Net-(LED113-C)") (class "Default")
      (node (ref "LED113") (pin "K") (pinfunction "C_K") (pintype "passive"))
      (node (ref "LED114") (pin "A") (pinfunction "A_A") (pintype "passive"))
    )
    (net (code "92") (name "Net-(LED114-C)") (class "Default")
      (node (ref "LED114") (pin "K") (pinfunction "C_K") (pintype "passive"))
      (node (ref "LED115") (pin "A") (pinfunction "A_A") (pintype "passive"))
    )
    (net (code "93") (name "Net-(LED115-C)") (class "Default")
      (node (ref "LED115") (pin "K") (pinfunction "C_K") (pintype "passive"))
      (node (ref "LED116") (pin "A") (pinfunction "A_A") (pintype "passive"))
    )
    (net (code "94") (name "Net-(LED116-C)") (class "Default")
      (node (ref "LED116") (pin "K") (pinfunction "C_K") (pintype "passive"))
      (node (ref "R36") (pin "2") (pinfunction "2_2") (pintype "passive"))
    )
    (net (code "95") (name "Net-(LED117-C)") (class "Default")
      (node (ref "LED117") (pin "K") (pinfunction "C_K") (pintype "passive"))
      (node (ref "LED118") (pin "A") (pinfunction "A_A") (pintype "passive"))
    )
    (net (code "96") (name "Net-(LED118-C)") (class "Default")
      (node (ref "LED118") (pin "K") (pinfunction "C_K") (pintype "passive"))
      (node (ref "LED119") (pin "A") (pinfunction "A_A") (pintype "passive"))
    )
    (net (code "97") (name "Net-(LED119-C)") (class "Default")
      (node (ref "LED119") (pin "K") (pinfunction "C_K") (pintype "passive"))
      (node (ref "LED120") (pin "A") (pinfunction "A_A") (pintype "passive"))
    )
    (net (code "98") (name "Net-(LED120-C)") (class "Default")
      (node (ref "LED120") (pin "K") (pinfunction "C_K") (pintype "passive"))
      (node (ref "R37") (pin "2") (pinfunction "2_2") (pintype "passive"))
    )
    (net (code "99") (name "Net-(LED121-C)") (class "Default")
      (node (ref "LED121") (pin "K") (pinfunction "C_K") (pintype "passive"))
      (node (ref "LED122") (pin "A") (pinfunction "A_A") (pintype "passive"))
    )
    (net (code "100") (name "Net-(LED122-C)") (class "Default")
      (node (ref "LED122") (pin "K") (pinfunction "C_K") (pintype "passive"))
      (node (ref "LED123") (pin "A") (pinfunction "A_A") (pintype "passive"))
    )
    (net (code "101") (name "Net-(LED123-C)") (class "Default")
      (node (ref "LED123") (pin "K") (pinfunction "C_K") (pintype "passive"))
      (node (ref "LED124") (pin "A") (pinfunction "A_A") (pintype "passive"))
    )
    (net (code "102") (name "Net-(LED124-C)") (class "Default")
      (node (ref "LED124") (pin "K") (pinfunction "C_K") (pintype "passive"))
      (node (ref "R38") (pin "2") (pinfunction "2_2") (pintype "passive"))
    )
    (net (code "103") (name "Net-(LED125-C)") (class "Default")
      (node (ref "LED125") (pin "K") (pinfunction "C_K") (pintype "passive"))
      (node (ref "LED126") (pin "A") (pinfunction "A_A") (pintype "passive"))
    )
    (net (code "104") (name "Net-(LED126-C)") (class "Default")
      (node (ref "LED126") (pin "K") (pinfunction "C_K") (pintype "passive"))
      (node (ref "LED127") (pin "A") (pinfunction "A_A") (pintype "passive"))
    )
    (net (code "105") (name "Net-(LED127-C)") (class "Default")
      (node (ref "LED127") (pin "K") (pinfunction "C_K") (pintype "passive"))
      (node (ref "LED128") (pin "A") (pinfunction "A_A") (pintype "passive"))
    )
    (net (code "106") (name "Net-(LED128-C)") (class "Default")
      (node (ref "LED128") (pin "K") (pinfunction "C_K") (pintype "passive"))
      (node (ref "R39") (pin "2") (pinfunction "2_2") (pintype "passive"))
    )
    (net (code "107") (name "Net-(LED129-C)") (class "Default")
      (node (ref "LED129") (pin "K") (pinfunction "C_K") (pintype "passive"))
      (node (ref "LED130") (pin "A") (pinfunction "A_A") (pintype "passive"))
    )
    (net (code "108") (name "Net-(LED130-C)") (class "Default")
      (node (ref "LED130") (pin "K") (pinfunction "C_K") (pintype "passive"))
      (node (ref "LED131") (pin "A") (pinfunction "A_A") (pintype "passive"))
    )
    (net (code "109") (name "Net-(LED131-C)") (class "Default")
      (node (ref "LED131") (pin "K") (pinfunction "C_K") (pintype "passive"))
      (node (ref "LED132") (pin "A") (pinfunction "A_A") (pintype "passive"))
    )
    (net (code "110") (name "Net-(LED132-C)") (class "Default")
      (node (ref "LED132") (pin "K") (pinfunction "C_K") (pintype "passive"))
      (node (ref "R41") (pin "2") (pinfunction "2_2") (pintype "passive"))
    )
    (net (code "111") (name "Net-(LED133-C)") (class "Default")
      (node (ref "LED133") (pin "K") (pinfunction "C_K") (pintype "passive"))
      (node (ref "LED134") (pin "A") (pinfunction "A_A") (pintype "passive"))
    )
    (net (code "112") (name "Net-(LED134-C)") (class "Default")
      (node (ref "LED134") (pin "K") (pinfunction "C_K") (pintype "passive"))
      (node (ref "LED135") (pin "A") (pinfunction "A_A") (pintype "passive"))
    )
    (net (code "113") (name "Net-(LED135-C)") (class "Default")
      (node (ref "LED135") (pin "K") (pinfunction "C_K") (pintype "passive"))
      (node (ref "LED136") (pin "A") (pinfunction "A_A") (pintype "passive"))
    )
    (net (code "114") (name "Net-(LED136-C)") (class "Default")
      (node (ref "LED136") (pin "K") (pinfunction "C_K") (pintype "passive"))
      (node (ref "R42") (pin "2") (pinfunction "2_2") (pintype "passive"))
    )
    (net (code "115") (name "Net-(LED137-C)") (class "Default")
      (node (ref "LED137") (pin "K") (pinfunction "C_K") (pintype "passive"))
      (node (ref "LED138") (pin "A") (pinfunction "A_A") (pintype "passive"))
    )
    (net (code "116") (name "Net-(LED138-C)") (class "Default")
      (node (ref "LED138") (pin "K") (pinfunction "C_K") (pintype "passive"))
      (node (ref "LED139") (pin "A") (pinfunction "A_A") (pintype "passive"))
    )
    (net (code "117") (name "Net-(LED139-C)") (class "Default")
      (node (ref "LED139") (pin "K") (pinfunction "C_K") (pintype "passive"))
      (node (ref "LED140") (pin "A") (pinfunction "A_A") (pintype "passive"))
    )
    (net (code "118") (name "Net-(LED140-C)") (class "Default")
      (node (ref "LED140") (pin "K") (pinfunction "C_K") (pintype "passive"))
      (node (ref "R43") (pin "2") (pinfunction "2_2") (pintype "passive"))
    )
    (net (code "119") (name "Net-(LED141-C)") (class "Default")
      (node (ref "LED141") (pin "K") (pinfunction "C_K") (pintype "passive"))
      (node (ref "LED142") (pin "A") (pinfunction "A_A") (pintype "passive"))
    )
    (net (code "120") (name "Net-(LED142-C)") (class "Default")
      (node (ref "LED142") (pin "K") (pinfunction "C_K") (pintype "passive"))
      (node (ref "LED143") (pin "A") (pinfunction "A_A") (pintype "passive"))
    )
    (net (code "121") (name "Net-(LED143-C)") (class "Default")
      (node (ref "LED143") (pin "K") (pinfunction "C_K") (pintype "passive"))
      (node (ref "LED144") (pin "A") (pinfunction "A_A") (pintype "passive"))
    )
    (net (code "122") (name "Net-(LED144-C)") (class "Default")
      (node (ref "LED144") (pin "K") (pinfunction "C_K") (pintype "passive"))
      (node (ref "R44") (pin "2") (pinfunction "2_2") (pintype "passive"))
    )
    (net (code "123") (name "Net-(T1-B)") (class "Default")
      (node (ref "R5") (pin "2") (pinfunction "2_2") (pintype "passive"))
      (node (ref "T1") (pin "2") (pinfunction "B_2") (pintype "passive"))
    )
    (net (code "124") (name "Net-(T1-C)") (class "Default")
      (node (ref "R1") (pin "1") (pinfunction "1_1") (pintype "passive"))
      (node (ref "R2") (pin "1") (pinfunction "1_1") (pintype "passive"))
      (node (ref "R3") (pin "1") (pinfunction "1_1") (pintype "passive"))
      (node (ref "R4") (pin "1") (pinfunction "1_1") (pintype "passive"))
      (node (ref "T1") (pin "3") (pinfunction "C_3") (pintype "passive"))
    )
    (net (code "125") (name "Net-(T1-E)") (class "Default")
      (node (ref "T1") (pin "1") (pinfunction "E_1") (pintype "passive"))
      (node (ref "T2") (pin "1") (pinfunction "E_1") (pintype "passive"))
      (node (ref "T3") (pin "1") (pinfunction "E_1") (pintype "passive"))
      (node (ref "T4") (pin "2") (pinfunction "C_2") (pintype "passive"))
      (node (ref "T6") (pin "1") (pinfunction "E_1") (pintype "passive"))
      (node (ref "T7") (pin "1") (pinfunction "E_1") (pintype "passive"))
      (node (ref "T8") (pin "1") (pinfunction "E_1") (pintype "passive"))
      (node (ref "T9") (pin "1") (pinfunction "E_1") (pintype "passive"))
    )
    (net (code "126") (name "Net-(T2-B)") (class "Default")
      (node (ref "R10") (pin "2") (pinfunction "2_2") (pintype "passive"))
      (node (ref "T2") (pin "2") (pinfunction "B_2") (pintype "passive"))
    )
    (net (code "127") (name "Net-(T2-C)") (class "Default")
      (node (ref "R6") (pin "1") (pinfunction "1_1") (pintype "passive"))
      (node (ref "R7") (pin "1") (pinfunction "1_1") (pintype "passive"))
      (node (ref "R8") (pin "1") (pinfunction "1_1") (pintype "passive"))
      (node (ref "R9") (pin "1") (pinfunction "1_1") (pintype "passive"))
      (node (ref "T2") (pin "3") (pinfunction "C_3") (pintype "passive"))
    )
    (net (code "128") (name "Net-(T3-B)") (class "Default")
      (node (ref "R15") (pin "2") (pinfunction "2_2") (pintype "passive"))
      (node (ref "T3") (pin "2") (pinfunction "B_2") (pintype "passive"))
    )
    (net (code "129") (name "Net-(T3-C)") (class "Default")
      (node (ref "R11") (pin "1") (pinfunction "1_1") (pintype "passive"))
      (node (ref "R12") (pin "1") (pinfunction "1_1") (pintype "passive"))
      (node (ref "R13") (pin "1") (pinfunction "1_1") (pintype "passive"))
      (node (ref "R14") (pin "1") (pinfunction "1_1") (pintype "passive"))
      (node (ref "T3") (pin "3") (pinfunction "C_3") (pintype "passive"))
    )
    (net (code "130") (name "Net-(T4-B)") (class "Default")
      (node (ref "R16") (pin "2") (pinfunction "2_2") (pintype "passive"))
      (node (ref "T4") (pin "3") (pinfunction "B_3") (pintype "passive"))
    )
    (net (code "131") (name "Net-(T6-B)") (class "Default")
      (node (ref "R30") (pin "2") (pinfunction "2_2") (pintype "passive"))
      (node (ref "T6") (pin "2") (pinfunction "B_2") (pintype "passive"))
    )
    (net (code "132") (name "Net-(T6-C)") (class "Default")
      (node (ref "R26") (pin "1") (pinfunction "1_1") (pintype "passive"))
      (node (ref "R27") (pin "1") (pinfunction "1_1") (pintype "passive"))
      (node (ref "R28") (pin "1") (pinfunction "1_1") (pintype "passive"))
      (node (ref "R29") (pin "1") (pinfunction "1_1") (pintype "passive"))
      (node (ref "T6") (pin "3") (pinfunction "C_3") (pintype "passive"))
    )
    (net (code "133") (name "Net-(T7-B)") (class "Default")
      (node (ref "R35") (pin "2") (pinfunction "2_2") (pintype "passive"))
      (node (ref "T7") (pin "2") (pinfunction "B_2") (pintype "passive"))
    )
    (net (code "134") (name "Net-(T7-C)") (class "Default")
      (node (ref "R31") (pin "1") (pinfunction "1_1") (pintype "passive"))
      (node (ref "R32") (pin "1") (pinfunction "1_1") (pintype "passive"))
      (node (ref "R33") (pin "1") (pinfunction "1_1") (pintype "passive"))
      (node (ref "R34") (pin "1") (pinfunction "1_1") (pintype "passive"))
      (node (ref "T7") (pin "3") (pinfunction "C_3") (pintype "passive"))
    )
    (net (code "135") (name "Net-(T8-B)") (class "Default")
      (node (ref "R40") (pin "2") (pinfunction "2_2") (pintype "passive"))
      (node (ref "T8") (pin "2") (pinfunction "B_2") (pintype "passive"))
    )
    (net (code "136") (name "Net-(T8-C)") (class "Default")
      (node (ref "R36") (pin "1") (pinfunction "1_1") (pintype "passive"))
      (node (ref "R37") (pin "1") (pinfunction "1_1") (pintype "passive"))
      (node (ref "R38") (pin "1") (pinfunction "1_1") (pintype "passive"))
      (node (ref "R39") (pin "1") (pinfunction "1_1") (pintype "passive"))
      (node (ref "T8") (pin "3") (pinfunction "C_3") (pintype "passive"))
    )
    (net (code "137") (name "Net-(T9-B)") (class "Default")
      (node (ref "R45") (pin "2") (pinfunction "2_2") (pintype "passive"))
      (node (ref "T9") (pin "2") (pinfunction "B_2") (pintype "passive"))
    )
    (net (code "138") (name "Net-(T9-C)") (class "Default")
      (node (ref "R41") (pin "1") (pinfunction "1_1") (pintype "passive"))
      (node (ref "R42") (pin "1") (pinfunction "1_1") (pintype "passive"))
      (node (ref "R43") (pin "1") (pinfunction "1_1") (pintype "passive"))
      (node (ref "R44") (pin "1") (pinfunction "1_1") (pintype "passive"))
      (node (ref "T9") (pin "3") (pinfunction "C_3") (pintype "passive"))
    )
  )
)
